# decawave.net
KiCad netlist of a schematic drawn in Altium Designer
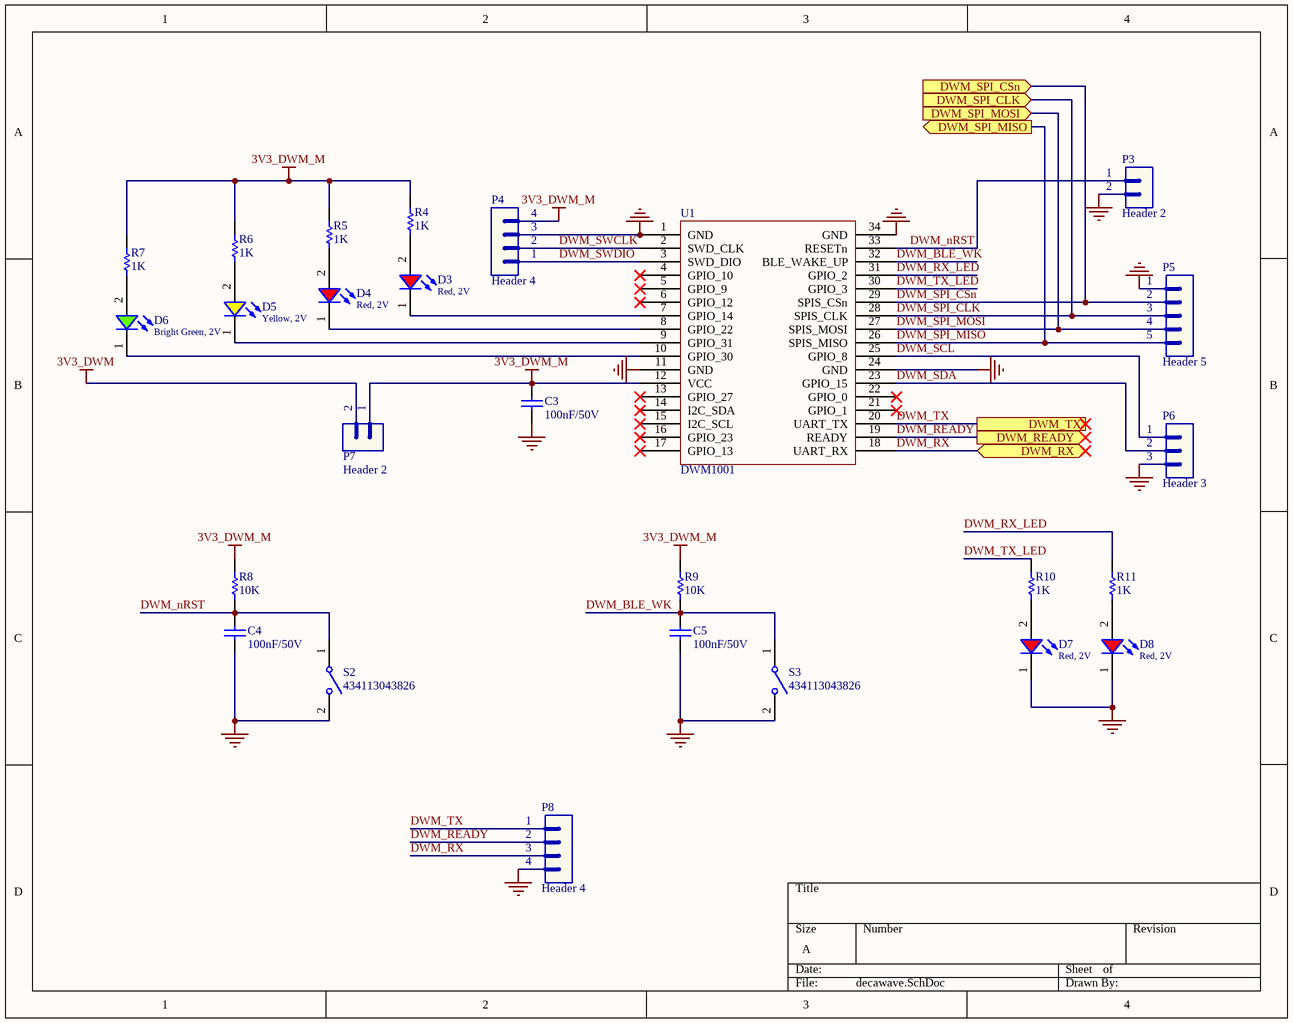
[diagram p0: decawave.SchDoc]

(export (version "E")
  (design (tool "Eeschema 10.0.6"))
  (components
    (comp (ref "C3")
      (value "100nF/50V")
      (footprint "CAP-SM-0805")
      (description "CAP CER 0.1UF 50V Y5V 0805")
      (fields
        (field (name "MANUFACTURER") "Samsung Electro-Mechanics")
        (field (name "MANUFACTURER PART NUMBER") "CL21F104ZBCNNNC")
      )
      (libsource (lib "Capacitor") (part "Cap-100nF-50V-0805"))
    )
    (comp (ref "C4")
      (value "100nF/50V")
      (footprint "CAP-SM-0805")
      (description "CAP CER 0.1UF 50V Y5V 0805")
      (fields
        (field (name "MANUFACTURER") "Samsung Electro-Mechanics")
        (field (name "MANUFACTURER PART NUMBER") "CL21F104ZBCNNNC")
      )
      (libsource (lib "Capacitor") (part "Cap-100nF-50V-0805"))
    )
    (comp (ref "C5")
      (value "100nF/50V")
      (footprint "CAP-SM-0805")
      (description "CAP CER 0.1UF 50V Y5V 0805")
      (fields
        (field (name "MANUFACTURER") "Samsung Electro-Mechanics")
        (field (name "MANUFACTURER PART NUMBER") "CL21F104ZBCNNNC")
      )
      (libsource (lib "Capacitor") (part "Cap-100nF-50V-0805"))
    )
    (comp (ref "D3")
      (value "Red, 2V")
      (footprint "WL-SMCW_0805")
      (description "WL-SMCW SMT Mono-color Chip LED Waterclear, size 0805, Red, 2V, 140deg")
      (fields (field (name "PART NUMBER") "150080RS75000") (field (name "PUBLISHER") "Wurth Elektronik"))
      (libsource (lib "150080BS75000_Altium_WL-SMCW_rev20a") (part "150080RS75000"))
    )
    (comp (ref "D4")
      (value "Red, 2V")
      (footprint "WL-SMCW_0805")
      (description "WL-SMCW SMT Mono-color Chip LED Waterclear, size 0805, Red, 2V, 140deg")
      (fields (field (name "PART NUMBER") "150080RS75000") (field (name "PUBLISHER") "Wurth Elektronik"))
      (libsource (lib "150080BS75000_Altium_WL-SMCW_rev20a") (part "150080RS75000"))
    )
    (comp (ref "D5")
      (value "Yellow, 2V")
      (footprint "WL-SMCW_0805")
      (description "WL-SMCW SMT Mono-color Chip LED Waterclear, size 0805, Yellow, 2V, 140deg")
      (fields (field (name "PART NUMBER") "150080YS75000") (field (name "PUBLISHER") "Wurth Elektronik"))
      (libsource (lib "150080BS75000_Altium_WL-SMCW_rev20a") (part "150080YS75000"))
    )
    (comp (ref "D6")
      (value "Bright Green, 2V")
      (footprint "WL-SMCW_0805")
      (description "WL-SMCW SMT Mono-color Chip LED Waterclear, size 0805, Bright Green, 2V, 140deg")
      (fields (field (name "PART NUMBER") "150080VS75000") (field (name "PUBLISHER") "Wurth Elektronik"))
      (libsource (lib "150080BS75000_Altium_WL-SMCW_rev20a") (part "150080VS75000"))
    )
    (comp (ref "D7")
      (value "Red, 2V")
      (footprint "WL-SMCW_0805")
      (description "WL-SMCW SMT Mono-color Chip LED Waterclear, size 0805, Red, 2V, 140deg")
      (fields (field (name "PART NUMBER") "150080RS75000") (field (name "PUBLISHER") "Wurth Elektronik"))
      (libsource (lib "150080BS75000_Altium_WL-SMCW_rev20a") (part "150080RS75000"))
    )
    (comp (ref "D8")
      (value "Red, 2V")
      (footprint "WL-SMCW_0805")
      (description "WL-SMCW SMT Mono-color Chip LED Waterclear, size 0805, Red, 2V, 140deg")
      (fields (field (name "PART NUMBER") "150080RS75000") (field (name "PUBLISHER") "Wurth Elektronik"))
      (libsource (lib "150080BS75000_Altium_WL-SMCW_rev20a") (part "150080RS75000"))
    )
    (comp (ref "P3")
      (value "Header 2")
      (footprint "JP2")
      (description "Header, 2-Pin")
      (fields (field (name "PUBLISHER") "Altium Limited"))
      (libsource (lib "PIF_C16_2_lib") (part "Header 2"))
    )
    (comp (ref "P4")
      (value "Header 4")
      (footprint "JP4")
      (description "Header, 4-Pin")
      (fields (field (name "PUBLISHER") "Altium Limited"))
      (libsource (lib "") (part "Header 4_1"))
    )
    (comp (ref "P5")
      (value "Header 5")
      (footprint "JP5")
      (description "Header, 5-Pin")
      (fields (field (name "PUBLISHER") "Altium Limited"))
      (libsource (lib "PIF_C16_2_lib") (part "Header 5"))
    )
    (comp (ref "P6")
      (value "Header 3")
      (footprint "JP3")
      (description "Header, 3-Pin")
      (fields (field (name "PUBLISHER") "Altium Limited"))
      (libsource (lib "PIF_C16_2_lib") (part "Header 3"))
    )
    (comp (ref "P7")
      (value "Header 2")
      (footprint "JP2")
      (description "Header, 2-Pin")
      (fields (field (name "PUBLISHER") "Altium Limited"))
      (libsource (lib "") (part "Header 2_1"))
    )
    (comp (ref "P8")
      (value "Header 4")
      (footprint "JP4")
      (description "Header, 4-Pin")
      (fields (field (name "PUBLISHER") "Altium Limited"))
      (libsource (lib "PIF_C16_2_lib") (part "Header 4"))
    )
    (comp (ref "R4")
      (value "1K")
      (footprint "Resistor:RES-SM-0805")
      (description "RES 1K OHM 1% 1/4W 0805")
      (fields
        (field (name "MANUFACTURER") "Stackpole Electronics Inc")
        (field (name "MANUFACTURER PART NUMBER") "RNCP0805FTD1K00")
      )
      (libsource (lib "Resistor") (part "Res-1K-0805"))
    )
    (comp (ref "R5")
      (value "1K")
      (footprint "Resistor:RES-SM-0805")
      (description "RES 1K OHM 1% 1/4W 0805")
      (fields
        (field (name "MANUFACTURER") "Stackpole Electronics Inc")
        (field (name "MANUFACTURER PART NUMBER") "RNCP0805FTD1K00")
      )
      (libsource (lib "Resistor") (part "Res-1K-0805"))
    )
    (comp (ref "R6")
      (value "1K")
      (footprint "Resistor:RES-SM-0805")
      (description "RES 1K OHM 1% 1/4W 0805")
      (fields
        (field (name "MANUFACTURER") "Stackpole Electronics Inc")
        (field (name "MANUFACTURER PART NUMBER") "RNCP0805FTD1K00")
      )
      (libsource (lib "Resistor") (part "Res-1K-0805"))
    )
    (comp (ref "R7")
      (value "1K")
      (footprint "Resistor:RES-SM-0805")
      (description "RES 1K OHM 1% 1/4W 0805")
      (fields
        (field (name "MANUFACTURER") "Stackpole Electronics Inc")
        (field (name "MANUFACTURER PART NUMBER") "RNCP0805FTD1K00")
      )
      (libsource (lib "Resistor") (part "Res-1K-0805"))
    )
    (comp (ref "R8")
      (value "10K")
      (footprint "Resistor:RES-SM-0805")
      (description "RES 10K OHM 1% 1/4W 0805")
      (fields
        (field (name "MANUFACTURER") "Stackpole Electronics Inc")
        (field (name "MANUFACTURER PART NUMBER") "RNCP0805FTD10K0")
      )
      (libsource (lib "Resistor") (part "Res-10k-0805"))
    )
    (comp (ref "R9")
      (value "10K")
      (footprint "Resistor:RES-SM-0805")
      (description "RES 10K OHM 1% 1/4W 0805")
      (fields
        (field (name "MANUFACTURER") "Stackpole Electronics Inc")
        (field (name "MANUFACTURER PART NUMBER") "RNCP0805FTD10K0")
      )
      (libsource (lib "Resistor") (part "Res-10k-0805"))
    )
    (comp (ref "R10")
      (value "1K")
      (footprint "Resistor:RES-SM-0805")
      (description "RES 1K OHM 1% 1/4W 0805")
      (fields
        (field (name "MANUFACTURER") "Stackpole Electronics Inc")
        (field (name "MANUFACTURER PART NUMBER") "RNCP0805FTD1K00")
      )
      (libsource (lib "Resistor") (part "Res-1K-0805"))
    )
    (comp (ref "R11")
      (value "1K")
      (footprint "Resistor:RES-SM-0805")
      (description "RES 1K OHM 1% 1/4W 0805")
      (fields
        (field (name "MANUFACTURER") "Stackpole Electronics Inc")
        (field (name "MANUFACTURER PART NUMBER") "RNCP0805FTD1K00")
      )
      (libsource (lib "Resistor") (part "Res-1K-0805"))
    )
    (comp (ref "S2")
      (value "434113043826")
      (footprint "434113043826")
      (description "WS-TASV J-Bend SMT Tact Switch 6x3.5mm, height 4.3mm, 260gf")
      (fields (field (name "PUBLISHER") "Wurth Elektronik"))
      (libsource (lib "434113043826_Altium_WS-TASV_rev20a") (part "434113043826"))
    )
    (comp (ref "S3")
      (value "434113043826")
      (footprint "434113043826")
      (description "WS-TASV J-Bend SMT Tact Switch 6x3.5mm, height 4.3mm, 260gf")
      (fields (field (name "PUBLISHER") "Wurth Elektronik"))
      (libsource (lib "434113043826_Altium_WS-TASV_rev20a") (part "434113043826"))
    )
    (comp (ref "U1") (value "DWM1001") (footprint "DWM1001") (libsource (lib "Schlib1") (part "DWM1001")))
  )
  (nets
    (net (code "1") (name "/DWM_BLE_WK") (class "Default")
      (node (ref "C5") (pin "2") (pinfunction "2_2") (pintype "passive"))
      (node (ref "R9") (pin "1") (pinfunction "1_1") (pintype "passive"))
      (node (ref "S3") (pin "1") (pinfunction "1_1") (pintype "passive"))
      (node (ref "U1") (pin "32") (pinfunction "BLE_WAKE_UP_32") (pintype "passive"))
    )
    (net (code "2") (name "/DWM_READY") (class "Default")
      (node (ref "P8") (pin "2") (pinfunction "2_2") (pintype "passive"))
      (node (ref "U1") (pin "19") (pinfunction "READY_19") (pintype "passive"))
    )
    (net (code "3") (name "/DWM_RX") (class "Default")
      (node (ref "P8") (pin "3") (pinfunction "3_3") (pintype "passive"))
      (node (ref "U1") (pin "18") (pinfunction "UART_RX_18") (pintype "passive"))
    )
    (net (code "4") (name "/DWM_RX_LED") (class "Default")
      (node (ref "R11") (pin "1") (pinfunction "1_1") (pintype "passive"))
      (node (ref "U1") (pin "31") (pinfunction "GPIO_2_31") (pintype "passive"))
    )
    (net (code "5") (name "/DWM_SCL") (class "Default")
      (node (ref "P6") (pin "1") (pinfunction "1_1") (pintype "passive"))
      (node (ref "U1") (pin "25") (pinfunction "GPIO_8_25") (pintype "passive"))
    )
    (net (code "6") (name "/DWM_SDA") (class "Default")
      (node (ref "P6") (pin "2") (pinfunction "2_2") (pintype "passive"))
      (node (ref "U1") (pin "23") (pinfunction "GPIO_15_23") (pintype "passive"))
    )
    (net (code "7") (name "/DWM_SPI_CLK") (class "Default")
      (node (ref "P5") (pin "3") (pinfunction "3_3") (pintype "passive"))
      (node (ref "U1") (pin "28") (pinfunction "SPIS_CLK_28") (pintype "passive"))
    )
    (net (code "8") (name "/DWM_SPI_CSn") (class "Default")
      (node (ref "P5") (pin "2") (pinfunction "2_2") (pintype "passive"))
      (node (ref "U1") (pin "29") (pinfunction "SPIS_CSn_29") (pintype "passive"))
    )
    (net (code "9") (name "/DWM_SPI_MISO") (class "Default")
      (node (ref "P5") (pin "5") (pinfunction "5_5") (pintype "passive"))
      (node (ref "U1") (pin "26") (pinfunction "SPIS_MISO_26") (pintype "passive"))
    )
    (net (code "10") (name "/DWM_SPI_MOSI") (class "Default")
      (node (ref "P5") (pin "4") (pinfunction "4_4") (pintype "passive"))
      (node (ref "U1") (pin "27") (pinfunction "SPIS_MOSI_27") (pintype "passive"))
    )
    (net (code "11") (name "/DWM_SWCLK") (class "Default")
      (node (ref "P4") (pin "2") (pinfunction "2_2") (pintype "passive"))
      (node (ref "U1") (pin "2") (pinfunction "SWD_CLK_2") (pintype "passive"))
    )
    (net (code "12") (name "/DWM_SWDIO") (class "Default")
      (node (ref "P4") (pin "1") (pinfunction "1_1") (pintype "passive"))
      (node (ref "U1") (pin "3") (pinfunction "SWD_DIO_3") (pintype "passive"))
    )
    (net (code "13") (name "/DWM_TX") (class "Default")
      (node (ref "P8") (pin "1") (pinfunction "1_1") (pintype "passive"))
      (node (ref "U1") (pin "20") (pinfunction "UART_TX_20") (pintype "passive"))
    )
    (net (code "14") (name "/DWM_TX_LED") (class "Default")
      (node (ref "R10") (pin "1") (pinfunction "1_1") (pintype "passive"))
      (node (ref "U1") (pin "30") (pinfunction "GPIO_3_30") (pintype "passive"))
    )
    (net (code "15") (name "/DWM_nRST") (class "Default")
      (node (ref "C4") (pin "2") (pinfunction "2_2") (pintype "passive"))
      (node (ref "P3") (pin "1") (pinfunction "1_1") (pintype "passive"))
      (node (ref "R8") (pin "1") (pinfunction "1_1") (pintype "passive"))
      (node (ref "S2") (pin "1") (pinfunction "1_1") (pintype "passive"))
      (node (ref "U1") (pin "33") (pinfunction "RESETn_33") (pintype "passive"))
    )
    (net (code "16") (name "3V3_DWM") (class "Default")
      (node (ref "P7") (pin "2") (pinfunction "2_2") (pintype "passive"))
    )
    (net (code "17") (name "3V3_DWM_M") (class "Default")
      (node (ref "C3") (pin "2") (pinfunction "2_2") (pintype "passive"))
      (node (ref "P4") (pin "4") (pinfunction "4_4") (pintype "passive"))
      (node (ref "P7") (pin "1") (pinfunction "1_1") (pintype "passive"))
      (node (ref "R4") (pin "1") (pinfunction "1_1") (pintype "passive"))
      (node (ref "R5") (pin "1") (pinfunction "1_1") (pintype "passive"))
      (node (ref "R6") (pin "1") (pinfunction "1_1") (pintype "passive"))
      (node (ref "R7") (pin "1") (pinfunction "1_1") (pintype "passive"))
      (node (ref "R8") (pin "2") (pinfunction "2_2") (pintype "passive"))
      (node (ref "R9") (pin "2") (pinfunction "2_2") (pintype "passive"))
      (node (ref "U1") (pin "12") (pinfunction "VCC_12") (pintype "passive"))
    )
    (net (code "18") (name "GND") (class "Default")
      (node (ref "C3") (pin "1") (pinfunction "1_1") (pintype "passive"))
      (node (ref "C4") (pin "1") (pinfunction "1_1") (pintype "passive"))
      (node (ref "C5") (pin "1") (pinfunction "1_1") (pintype "passive"))
      (node (ref "D7") (pin "1") (pinfunction "K_1") (pintype "passive"))
      (node (ref "D8") (pin "1") (pinfunction "K_1") (pintype "passive"))
      (node (ref "P3") (pin "2") (pinfunction "2_2") (pintype "passive"))
      (node (ref "P4") (pin "3") (pinfunction "3_3") (pintype "passive"))
      (node (ref "P5") (pin "1") (pinfunction "1_1") (pintype "passive"))
      (node (ref "P6") (pin "3") (pinfunction "3_3") (pintype "passive"))
      (node (ref "P8") (pin "4") (pinfunction "4_4") (pintype "passive"))
      (node (ref "S2") (pin "2") (pinfunction "2_2") (pintype "passive"))
      (node (ref "S3") (pin "2") (pinfunction "2_2") (pintype "passive"))
      (node (ref "U1") (pin "1") (pinfunction "GND_1") (pintype "passive"))
      (node (ref "U1") (pin "11") (pinfunction "GND_11") (pintype "passive"))
      (node (ref "U1") (pin "24") (pinfunction "GND_24") (pintype "passive"))
      (node (ref "U1") (pin "34") (pinfunction "GND_34") (pintype "passive"))
    )
    (net (code "19") (name "Net-(D3-A)") (class "Default")
      (node (ref "D3") (pin "2") (pinfunction "A_2") (pintype "passive"))
      (node (ref "R4") (pin "2") (pinfunction "2_2") (pintype "passive"))
    )
    (net (code "20") (name "Net-(D3-K)") (class "Default")
      (node (ref "D3") (pin "1") (pinfunction "K_1") (pintype "passive"))
      (node (ref "U1") (pin "7") (pinfunction "GPIO_14_7") (pintype "passive"))
    )
    (net (code "21") (name "Net-(D4-A)") (class "Default")
      (node (ref "D4") (pin "2") (pinfunction "A_2") (pintype "passive"))
      (node (ref "R5") (pin "2") (pinfunction "2_2") (pintype "passive"))
    )
    (net (code "22") (name "Net-(D4-K)") (class "Default")
      (node (ref "D4") (pin "1") (pinfunction "K_1") (pintype "passive"))
      (node (ref "U1") (pin "8") (pinfunction "GPIO_22_8") (pintype "passive"))
    )
    (net (code "23") (name "Net-(D5-A)") (class "Default")
      (node (ref "D5") (pin "2") (pinfunction "A_2") (pintype "passive"))
      (node (ref "R6") (pin "2") (pinfunction "2_2") (pintype "passive"))
    )
    (net (code "24") (name "Net-(D5-K)") (class "Default")
      (node (ref "D5") (pin "1") (pinfunction "K_1") (pintype "passive"))
      (node (ref "U1") (pin "9") (pinfunction "GPIO_31_9") (pintype "passive"))
    )
    (net (code "25") (name "Net-(D6-A)") (class "Default")
      (node (ref "D6") (pin "2") (pinfunction "A_2") (pintype "passive"))
      (node (ref "R7") (pin "2") (pinfunction "2_2") (pintype "passive"))
    )
    (net (code "26") (name "Net-(D6-K)") (class "Default")
      (node (ref "D6") (pin "1") (pinfunction "K_1") (pintype "passive"))
      (node (ref "U1") (pin "10") (pinfunction "GPIO_30_10") (pintype "passive"))
    )
    (net (code "27") (name "Net-(D7-A)") (class "Default")
      (node (ref "D7") (pin "2") (pinfunction "A_2") (pintype "passive"))
      (node (ref "R10") (pin "2") (pinfunction "2_2") (pintype "passive"))
    )
    (net (code "28") (name "Net-(D8-A)") (class "Default")
      (node (ref "D8") (pin "2") (pinfunction "A_2") (pintype "passive"))
      (node (ref "R11") (pin "2") (pinfunction "2_2") (pintype "passive"))
    )
    (net (code "29") (name "unconnected-(U1-GPIO_0-Pad22)") (class "Default")
      (node (ref "U1") (pin "22") (pinfunction "GPIO_0_22") (pintype "passive+no_connect"))
    )
    (net (code "30") (name "unconnected-(U1-GPIO_1-Pad21)") (class "Default")
      (node (ref "U1") (pin "21") (pinfunction "GPIO_1_21") (pintype "passive+no_connect"))
    )
    (net (code "31") (name "unconnected-(U1-GPIO_9-Pad5)") (class "Default")
      (node (ref "U1") (pin "5") (pinfunction "GPIO_9_5") (pintype "passive+no_connect"))
    )
    (net (code "32") (name "unconnected-(U1-GPIO_10-Pad4)") (class "Default")
      (node (ref "U1") (pin "4") (pinfunction "GPIO_10_4") (pintype "passive+no_connect"))
    )
    (net (code "33") (name "unconnected-(U1-GPIO_12-Pad6)") (class "Default")
      (node (ref "U1") (pin "6") (pinfunction "GPIO_12_6") (pintype "passive+no_connect"))
    )
    (net (code "34") (name "unconnected-(U1-GPIO_13-Pad17)") (class "Default")
      (node (ref "U1") (pin "17") (pinfunction "GPIO_13_17") (pintype "passive+no_connect"))
    )
    (net (code "35") (name "unconnected-(U1-GPIO_23-Pad16)") (class "Default")
      (node (ref "U1") (pin "16") (pinfunction "GPIO_23_16") (pintype "passive+no_connect"))
    )
    (net (code "36") (name "unconnected-(U1-GPIO_27-Pad13)") (class "Default")
      (node (ref "U1") (pin "13") (pinfunction "GPIO_27_13") (pintype "passive+no_connect"))
    )
    (net (code "37") (name "unconnected-(U1-I2C_SCL-Pad15)") (class "Default")
      (node (ref "U1") (pin "15") (pinfunction "I2C_SCL_15") (pintype "passive+no_connect"))
    )
    (net (code "38") (name "unconnected-(U1-I2C_SDA-Pad14)") (class "Default")
      (node (ref "U1") (pin "14") (pinfunction "I2C_SDA_14") (pintype "passive+no_connect"))
    )
  )
)
